# Power.net
KiCad netlist of a schematic drawn in Altium Designer
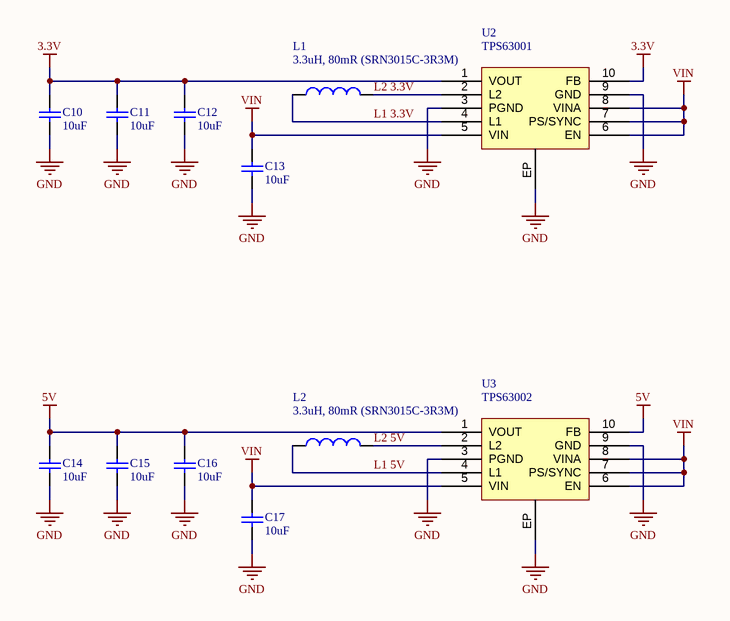
[diagram p0: Power.SchDoc]

(export (version "E")
  (design (tool "Eeschema 10.0.6"))
  (components
    (comp (ref "C10") (value "10uF") (footprint "Capacitor 0402") (libsource (lib "x-io") (part "Capacitor")))
    (comp (ref "C11") (value "10uF") (footprint "Capacitor 0402") (libsource (lib "x-io") (part "Capacitor")))
    (comp (ref "C12") (value "10uF") (footprint "Capacitor 0402") (libsource (lib "x-io") (part "Capacitor")))
    (comp (ref "C13") (value "10uF") (footprint "Capacitor 0402") (libsource (lib "x-io") (part "Capacitor")))
    (comp (ref "C14") (value "10uF") (footprint "Capacitor 0402") (libsource (lib "x-io") (part "Capacitor")))
    (comp (ref "C15") (value "10uF") (footprint "Capacitor 0402") (libsource (lib "x-io") (part "Capacitor")))
    (comp (ref "C16") (value "10uF") (footprint "Capacitor 0402") (libsource (lib "x-io") (part "Capacitor")))
    (comp (ref "C17") (value "10uF") (footprint "Capacitor 0402") (libsource (lib "x-io") (part "Capacitor")))
    (comp (ref "L1")
      (value "3.3uH, 80mR (SRN3015C-3R3M)")
      (footprint "SRN3015C")
      (libsource (lib "x-io") (part "Inductor"))
    )
    (comp (ref "L2")
      (value "3.3uH, 80mR (SRN3015C-3R3M)")
      (footprint "SRN3015C")
      (libsource (lib "x-io") (part "Inductor"))
    )
    (comp (ref "U2") (value "TPS63001") (footprint "VSON-10") (libsource (lib "x-io") (part "TPS630XX")))
    (comp (ref "U3") (value "TPS63002") (footprint "VSON-10") (libsource (lib "x-io") (part "TPS630XX")))
  )
  (nets
    (net (code "1") (name "/L1 3.3V") (class "Default")
      (node (ref "L1") (pin "1") (pinfunction "1_1") (pintype "passive"))
      (node (ref "U2") (pin "4") (pinfunction "L1_4") (pintype "passive"))
    )
    (net (code "2") (name "/L1 5V") (class "Default")
      (node (ref "L2") (pin "1") (pinfunction "1_1") (pintype "passive"))
      (node (ref "U3") (pin "4") (pinfunction "L1_4") (pintype "passive"))
    )
    (net (code "3") (name "/L2 3.3V") (class "Default")
      (node (ref "L1") (pin "2") (pinfunction "2_2") (pintype "passive"))
      (node (ref "U2") (pin "2") (pinfunction "L2_2") (pintype "passive"))
    )
    (net (code "4") (name "/L2 5V") (class "Default")
      (node (ref "L2") (pin "2") (pinfunction "2_2") (pintype "passive"))
      (node (ref "U3") (pin "2") (pinfunction "L2_2") (pintype "passive"))
    )
    (net (code "5") (name "3.3V") (class "Default")
      (node (ref "C10") (pin "2") (pinfunction "2_2") (pintype "passive"))
      (node (ref "C11") (pin "2") (pinfunction "2_2") (pintype "passive"))
      (node (ref "C12") (pin "2") (pinfunction "2_2") (pintype "passive"))
      (node (ref "U2") (pin "1") (pinfunction "VOUT_1") (pintype "passive"))
      (node (ref "U2") (pin "10") (pinfunction "FB_10") (pintype "passive"))
    )
    (net (code "6") (name "5V") (class "Default")
      (node (ref "C14") (pin "2") (pinfunction "2_2") (pintype "passive"))
      (node (ref "C15") (pin "2") (pinfunction "2_2") (pintype "passive"))
      (node (ref "C16") (pin "2") (pinfunction "2_2") (pintype "passive"))
      (node (ref "U3") (pin "1") (pinfunction "VOUT_1") (pintype "passive"))
      (node (ref "U3") (pin "10") (pinfunction "FB_10") (pintype "passive"))
    )
    (net (code "7") (name "GND") (class "Default")
      (node (ref "C10") (pin "1") (pinfunction "1_1") (pintype "passive"))
      (node (ref "C11") (pin "1") (pinfunction "1_1") (pintype "passive"))
      (node (ref "C12") (pin "1") (pinfunction "1_1") (pintype "passive"))
      (node (ref "C13") (pin "1") (pinfunction "1_1") (pintype "passive"))
      (node (ref "C14") (pin "1") (pinfunction "1_1") (pintype "passive"))
      (node (ref "C15") (pin "1") (pinfunction "1_1") (pintype "passive"))
      (node (ref "C16") (pin "1") (pinfunction "1_1") (pintype "passive"))
      (node (ref "C17") (pin "1") (pinfunction "1_1") (pintype "passive"))
      (node (ref "U2") (pin "3") (pinfunction "PGND_3") (pintype "passive"))
      (node (ref "U2") (pin "9") (pinfunction "GND_9") (pintype "passive"))
      (node (ref "U2") (pin "EP") (pinfunction "EP_EP") (pintype "passive"))
      (node (ref "U3") (pin "3") (pinfunction "PGND_3") (pintype "passive"))
      (node (ref "U3") (pin "9") (pinfunction "GND_9") (pintype "passive"))
      (node (ref "U3") (pin "EP") (pinfunction "EP_EP") (pintype "passive"))
    )
    (net (code "8") (name "VIN") (class "Default")
      (node (ref "C13") (pin "2") (pinfunction "2_2") (pintype "passive"))
      (node (ref "C17") (pin "2") (pinfunction "2_2") (pintype "passive"))
      (node (ref "U2") (pin "5") (pinfunction "VIN_5") (pintype "passive"))
      (node (ref "U2") (pin "6") (pinfunction "EN_6") (pintype "passive"))
      (node (ref "U2") (pin "7") (pinfunction "PS/SYNC_7") (pintype "passive"))
      (node (ref "U2") (pin "8") (pinfunction "VINA_8") (pintype "passive"))
      (node (ref "U3") (pin "5") (pinfunction "VIN_5") (pintype "passive"))
      (node (ref "U3") (pin "6") (pinfunction "EN_6") (pintype "passive"))
      (node (ref "U3") (pin "7") (pinfunction "PS/SYNC_7") (pintype "passive"))
      (node (ref "U3") (pin "8") (pinfunction "VINA_8") (pintype "passive"))
    )
  )
)
